# GeekGatheringIot.net
KiCad netlist of a schematic drawn in EAGLE
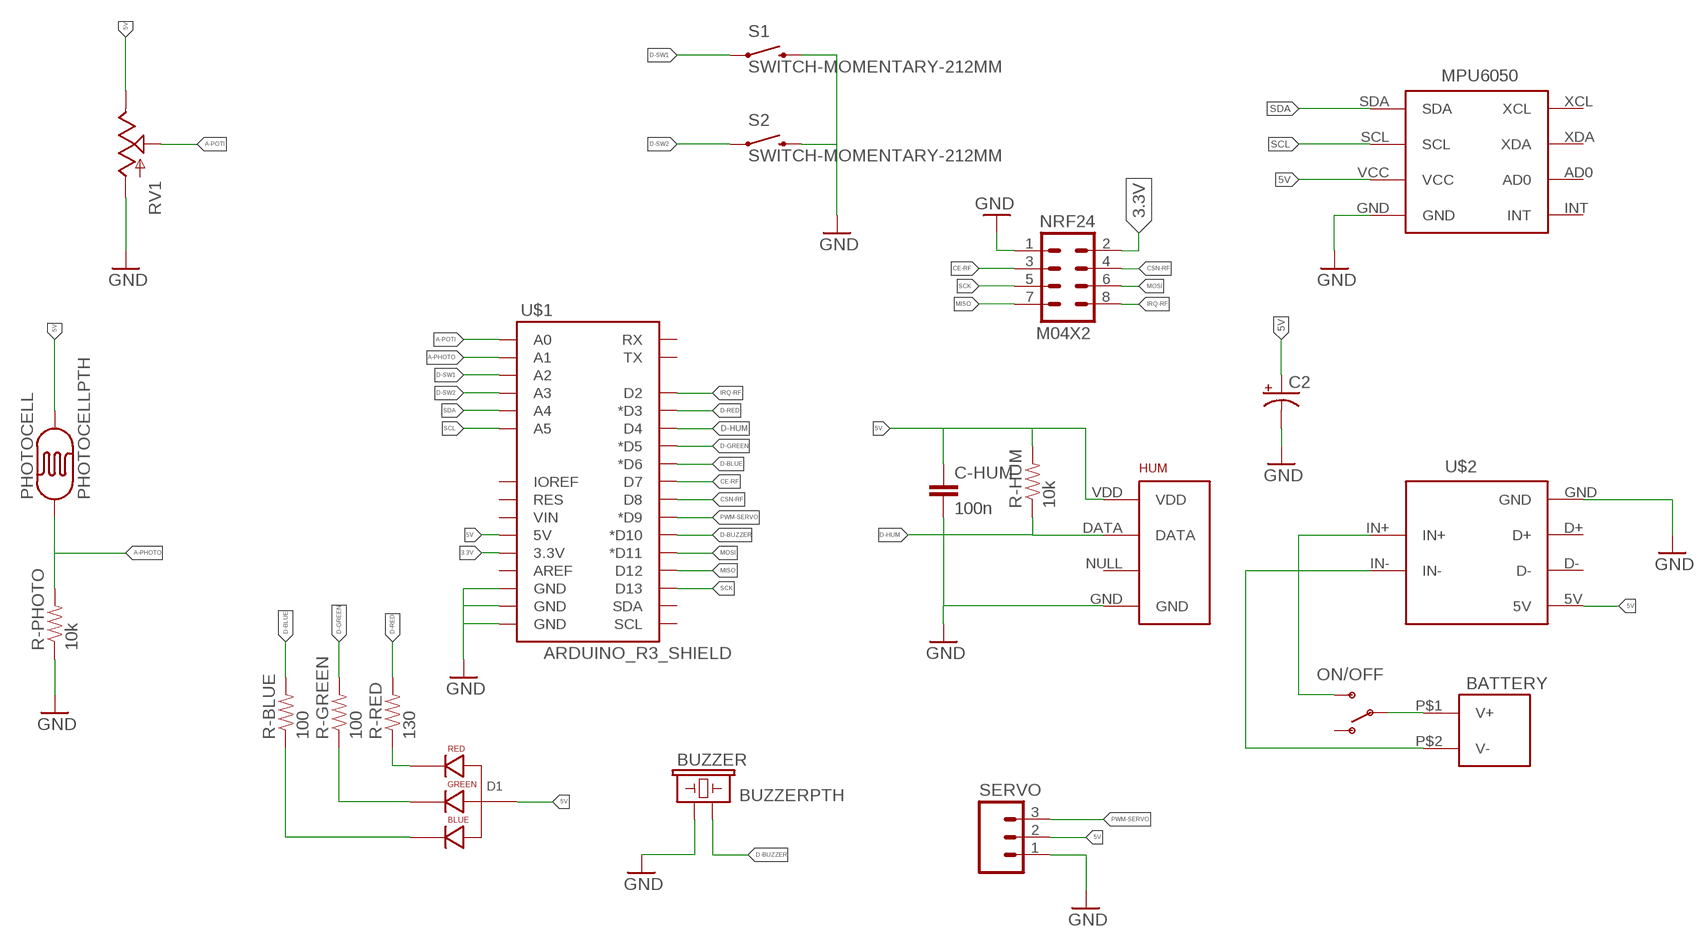
[diagram p0: schematic, sheet 1]

(export (version "E")
  (design (tool "Eeschema 10.0.6"))
  (components
    (comp (ref "BATTERY")
      (value "BATTERY-PACKAAA")
      (footprint "eagle-import:BATTERY-PACK")
      (libsource (lib "eagle-import") (part "BATTERY-PACKAAA"))
    )
    (comp (ref "BUZZER")
      (value "BUZZERPTH")
      (footprint "eagle-import:BUZZER-12MM")
      (libsource (lib "eagle-import") (part "BUZZERPTH"))
    )
    (comp (ref "C-HUM")
      (value "100n")
      (footprint "eagle-import:CAP-PTH-SMALL")
      (libsource (lib "eagle-import") (part "CAPPTH"))
    )
    (comp (ref "C2")
      (value "CAP_POLPTH2")
      (footprint "eagle-import:CPOL-RADIAL-10UF-25V")
      (libsource (lib "eagle-import") (part "CAP_POLPTH2"))
    )
    (comp (ref "D1")
      (value "LED-RGB-CA-THRUCLEAR")
      (footprint "eagle-import:LED-RGB-THRU")
      (libsource (lib "eagle-import") (part "LED-RGB-CA-THRUCLEAR"))
    )
    (comp (ref "HUM")
      (value "RHT03_DHT-22_AM2302")
      (footprint "eagle-import:RHT03_DHT-22")
      (libsource (lib "eagle-import") (part "RHT03_DHT-22_AM2302"))
    )
    (comp (ref "MPU6050")
      (value "MPU6050")
      (footprint "eagle-import:MPU6050")
      (libsource (lib "eagle-import") (part "MPU6050"))
    )
    (comp (ref "NRF24")
      (value "M04X2")
      (footprint "eagle-import:2X4")
      (libsource (lib "eagle-import") (part "M04X2"))
    )
    (comp (ref "ON/OFF")
      (value "SWITCH-SPDTPTH")
      (footprint "eagle-import:SWITCH-SPDT")
      (libsource (lib "eagle-import") (part "SWITCH-SPDTPTH"))
    )
    (comp (ref "PHOTOCELL")
      (value "PHOTOCELLPTH")
      (footprint "eagle-import:PHOTOCELL")
      (libsource (lib "eagle-import") (part "PHOTOCELLPTH"))
    )
    (comp (ref "R-BLUE")
      (value "100")
      (footprint "eagle-import:AXIAL-0.5")
      (libsource (lib "eagle-import") (part "RESISTORPTH-1/2W"))
    )
    (comp (ref "R-GREEN")
      (value "100")
      (footprint "eagle-import:AXIAL-0.5")
      (libsource (lib "eagle-import") (part "RESISTORPTH-1/2W"))
    )
    (comp (ref "R-HUM")
      (value "10k")
      (footprint "eagle-import:AXIAL-0.5")
      (libsource (lib "eagle-import") (part "RESISTORPTH-1/2W"))
    )
    (comp (ref "R-PHOTO")
      (value "10k")
      (footprint "eagle-import:AXIAL-0.5")
      (libsource (lib "eagle-import") (part "RESISTORPTH-1/2W"))
    )
    (comp (ref "R-RED")
      (value "130")
      (footprint "eagle-import:AXIAL-0.5")
      (libsource (lib "eagle-import") (part "RESISTORPTH-1/2W"))
    )
    (comp (ref "RV1")
      (value "POT-RV16AF-20")
      (footprint "eagle-import:POT_ALPHA_RV16AF-20")
      (libsource (lib "eagle-import") (part "POT-RV16AF-20"))
    )
    (comp (ref "S1")
      (value "SWITCH-MOMENTARY-212MM")
      (footprint "eagle-import:TACTILE-PTH-12MM")
      (libsource (lib "eagle-import") (part "SWITCH-MOMENTARY-212MM"))
    )
    (comp (ref "S2")
      (value "SWITCH-MOMENTARY-212MM")
      (footprint "eagle-import:TACTILE-PTH-12MM")
      (libsource (lib "eagle-import") (part "SWITCH-MOMENTARY-212MM"))
    )
    (comp (ref "SERVO")
      (value "M03PTH")
      (footprint "eagle-import:1X03")
      (libsource (lib "eagle-import") (part "M03PTH"))
    )
    (comp (ref "U$1")
      (value "ARDUINO_R3_SHIELD")
      (footprint "eagle-import:UNO_R3_SHIELD")
      (libsource (lib "eagle-import") (part "ARDUINO_R3_SHIELD"))
    )
    (comp (ref "U$2")
      (value "DC-DC-5V")
      (footprint "eagle-import:DC-DC-5V")
      (libsource (lib "eagle-import") (part "DC-DC-5V"))
    )
  )
  (nets
    (net (code "1") (name "3.3V") (class "Default")
      (node (ref "NRF24") (pin "2") (pinfunction "2_2") (pintype "passive"))
      (node (ref "U$1") (pin "3.3V") (pinfunction "3.3V_3.3V") (pintype "bidirectional"))
    )
    (net (code "2") (name "5V") (class "Default")
      (node (ref "C-HUM") (pin "1") (pinfunction "1_1") (pintype "passive"))
      (node (ref "C2") (pin "1") (pinfunction "+_1") (pintype "passive"))
      (node (ref "D1") (pin "2") (pinfunction "ANODE_2") (pintype "bidirectional"))
      (node (ref "HUM") (pin "VDD") (pinfunction "VDD_VDD") (pintype "power_in"))
      (node (ref "MPU6050") (pin "VCC") (pinfunction "VCC_VCC") (pintype "bidirectional"))
      (node (ref "PHOTOCELL") (pin "2") (pinfunction "P$2_2") (pintype "bidirectional"))
      (node (ref "R-HUM") (pin "P$2") (pinfunction "2_P$2") (pintype "passive"))
      (node (ref "RV1") (pin "3") (pinfunction "E_3") (pintype "passive"))
      (node (ref "SERVO") (pin "2") (pinfunction "2_2") (pintype "passive"))
      (node (ref "U$1") (pin "5V") (pinfunction "5V_5V") (pintype "bidirectional"))
      (node (ref "U$2") (pin "5V") (pinfunction "5V_5V") (pintype "bidirectional"))
    )
    (net (code "3") (name "A-PHOTO") (class "Default")
      (node (ref "PHOTOCELL") (pin "1") (pinfunction "P$1_1") (pintype "bidirectional"))
      (node (ref "R-PHOTO") (pin "P$2") (pinfunction "2_P$2") (pintype "passive"))
      (node (ref "U$1") (pin "A1") (pinfunction "A1_A1") (pintype "bidirectional"))
    )
    (net (code "4") (name "A-POTI") (class "Default")
      (node (ref "RV1") (pin "2") (pinfunction "S_2") (pintype "passive"))
      (node (ref "U$1") (pin "A0") (pinfunction "A0_A0") (pintype "bidirectional"))
    )
    (net (code "5") (name "CE-RF") (class "Default")
      (node (ref "NRF24") (pin "3") (pinfunction "3_3") (pintype "passive"))
      (node (ref "U$1") (pin "D7") (pinfunction "D7_D7") (pintype "bidirectional"))
    )
    (net (code "6") (name "CSN-RF") (class "Default")
      (node (ref "NRF24") (pin "4") (pinfunction "4_4") (pintype "passive"))
      (node (ref "U$1") (pin "D8") (pinfunction "D8_D8") (pintype "bidirectional"))
    )
    (net (code "7") (name "D-BLUE") (class "Default")
      (node (ref "R-BLUE") (pin "P$2") (pinfunction "2_P$2") (pintype "passive"))
      (node (ref "U$1") (pin "D6") (pinfunction "*D6_D6") (pintype "bidirectional"))
    )
    (net (code "8") (name "D-BUZZER") (class "Default")
      (node (ref "BUZZER") (pin "-") (pinfunction "2_-") (pintype "passive"))
      (node (ref "U$1") (pin "D10") (pinfunction "*D10_D10") (pintype "bidirectional"))
    )
    (net (code "9") (name "D-GREEN") (class "Default")
      (node (ref "R-GREEN") (pin "P$2") (pinfunction "2_P$2") (pintype "passive"))
      (node (ref "U$1") (pin "D5") (pinfunction "*D5_D5") (pintype "bidirectional"))
    )
    (net (code "10") (name "D-HUM") (class "Default")
      (node (ref "HUM") (pin "DATA") (pinfunction "DATA_DATA") (pintype "bidirectional"))
      (node (ref "R-HUM") (pin "P$1") (pinfunction "1_P$1") (pintype "passive"))
      (node (ref "U$1") (pin "D4") (pinfunction "D4_D4") (pintype "bidirectional"))
    )
    (net (code "11") (name "D-RED") (class "Default")
      (node (ref "R-RED") (pin "P$2") (pinfunction "2_P$2") (pintype "passive"))
      (node (ref "U$1") (pin "D3") (pinfunction "*D3_D3") (pintype "bidirectional"))
    )
    (net (code "12") (name "D-SW1") (class "Default")
      (node (ref "S1") (pin "1") (pinfunction "1_1") (pintype "passive"))
      (node (ref "U$1") (pin "A2") (pinfunction "A2_A2") (pintype "bidirectional"))
    )
    (net (code "13") (name "D-SW2") (class "Default")
      (node (ref "S2") (pin "1") (pinfunction "1_1") (pintype "passive"))
      (node (ref "U$1") (pin "A3") (pinfunction "A3_A3") (pintype "bidirectional"))
    )
    (net (code "14") (name "GND") (class "Default")
      (node (ref "BUZZER") (pin "+") (pinfunction "1_+") (pintype "passive"))
      (node (ref "C-HUM") (pin "2") (pinfunction "2_2") (pintype "passive"))
      (node (ref "C2") (pin "2") (pinfunction "-_2") (pintype "passive"))
      (node (ref "HUM") (pin "GND") (pinfunction "GND_GND") (pintype "power_in"))
      (node (ref "MPU6050") (pin "GND") (pinfunction "GND_GND") (pintype "bidirectional"))
      (node (ref "NRF24") (pin "1") (pinfunction "1_1") (pintype "passive"))
      (node (ref "R-PHOTO") (pin "P$1") (pinfunction "1_P$1") (pintype "passive"))
      (node (ref "RV1") (pin "1") (pinfunction "A_1") (pintype "passive"))
      (node (ref "S1") (pin "3") (pinfunction "2_3") (pintype "passive"))
      (node (ref "S2") (pin "3") (pinfunction "2_3") (pintype "passive"))
      (node (ref "SERVO") (pin "1") (pinfunction "1_1") (pintype "passive"))
      (node (ref "U$1") (pin "GND@0") (pinfunction "GND_GND@0") (pintype "bidirectional"))
      (node (ref "U$1") (pin "GND@1") (pinfunction "GND_GND@1") (pintype "bidirectional"))
      (node (ref "U$1") (pin "GND@2") (pinfunction "GND_GND@2") (pintype "bidirectional"))
      (node (ref "U$2") (pin "GND") (pinfunction "GND_GND") (pintype "bidirectional"))
    )
    (net (code "15") (name "IRQ-RF") (class "Default")
      (node (ref "NRF24") (pin "8") (pinfunction "8_8") (pintype "passive"))
      (node (ref "U$1") (pin "D2") (pinfunction "D2_D2") (pintype "bidirectional"))
    )
    (net (code "16") (name "MISO") (class "Default")
      (node (ref "NRF24") (pin "7") (pinfunction "7_7") (pintype "passive"))
      (node (ref "U$1") (pin "D12") (pinfunction "D12_D12") (pintype "bidirectional"))
    )
    (net (code "17") (name "MOSI") (class "Default")
      (node (ref "NRF24") (pin "6") (pinfunction "6_6") (pintype "passive"))
      (node (ref "U$1") (pin "D11") (pinfunction "*D11_D11") (pintype "bidirectional"))
    )
    (net (code "18") (name "Net-(BATTERY-V+)") (class "Default")
      (node (ref "BATTERY") (pin "P$1") (pinfunction "V+_P$1") (pintype "bidirectional"))
      (node (ref "ON/OFF") (pin "2") (pinfunction "P_2") (pintype "passive"))
    )
    (net (code "19") (name "Net-(BATTERY-V-)") (class "Default")
      (node (ref "BATTERY") (pin "P$2") (pinfunction "V-_P$2") (pintype "bidirectional"))
      (node (ref "U$2") (pin "IN-") (pinfunction "IN-_IN-") (pintype "bidirectional"))
    )
    (net (code "20") (name "Net-(D1-BLUE_CATHODE)") (class "Default")
      (node (ref "D1") (pin "4") (pinfunction "BLUE_CATHODE_4") (pintype "bidirectional"))
      (node (ref "R-BLUE") (pin "P$1") (pinfunction "1_P$1") (pintype "passive"))
    )
    (net (code "21") (name "Net-(D1-GREEN_CATHODE)") (class "Default")
      (node (ref "D1") (pin "3") (pinfunction "GREEN_CATHODE_3") (pintype "bidirectional"))
      (node (ref "R-GREEN") (pin "P$1") (pinfunction "1_P$1") (pintype "passive"))
    )
    (net (code "22") (name "Net-(D1-RED_CATHODE)") (class "Default")
      (node (ref "D1") (pin "1") (pinfunction "RED_CATHODE_1") (pintype "bidirectional"))
      (node (ref "R-RED") (pin "P$1") (pinfunction "1_P$1") (pintype "passive"))
    )
    (net (code "23") (name "Net-(ON/OFF-S)") (class "Default")
      (node (ref "ON/OFF") (pin "3") (pinfunction "S_3") (pintype "passive"))
      (node (ref "U$2") (pin "IN+") (pinfunction "IN+_IN+") (pintype "bidirectional"))
    )
    (net (code "24") (name "PWM-SERVO") (class "Default")
      (node (ref "SERVO") (pin "3") (pinfunction "3_3") (pintype "passive"))
      (node (ref "U$1") (pin "D9") (pinfunction "*D9_D9") (pintype "bidirectional"))
    )
    (net (code "25") (name "SCK") (class "Default")
      (node (ref "NRF24") (pin "5") (pinfunction "5_5") (pintype "passive"))
      (node (ref "U$1") (pin "D13") (pinfunction "D13_D13") (pintype "bidirectional"))
    )
    (net (code "26") (name "SCL") (class "Default")
      (node (ref "MPU6050") (pin "SCL") (pinfunction "SCL_SCL") (pintype "bidirectional"))
      (node (ref "U$1") (pin "A5") (pinfunction "A5_A5") (pintype "bidirectional"))
    )
    (net (code "27") (name "SDA") (class "Default")
      (node (ref "MPU6050") (pin "SDA") (pinfunction "SDA_SDA") (pintype "bidirectional"))
      (node (ref "U$1") (pin "A4") (pinfunction "A4_A4") (pintype "bidirectional"))
    )
    (net (code "28") (name "unconnected-(HUM-PadNULL)") (class "Default")
      (node (ref "HUM") (pin "NULL") (pinfunction "NULL_NULL") (pintype "no_connect"))
    )
    (net (code "29") (name "unconnected-(MPU6050-PadAD0)") (class "Default")
      (node (ref "MPU6050") (pin "AD0") (pinfunction "AD0_AD0") (pintype "bidirectional"))
    )
    (net (code "30") (name "unconnected-(MPU6050-PadINT)") (class "Default")
      (node (ref "MPU6050") (pin "INT") (pinfunction "INT_INT") (pintype "bidirectional"))
    )
    (net (code "31") (name "unconnected-(MPU6050-PadXCL)") (class "Default")
      (node (ref "MPU6050") (pin "XCL") (pinfunction "XCL_XCL") (pintype "bidirectional"))
    )
    (net (code "32") (name "unconnected-(MPU6050-PadXDA)") (class "Default")
      (node (ref "MPU6050") (pin "XDA") (pinfunction "XDA_XDA") (pintype "bidirectional"))
    )
    (net (code "33") (name "unconnected-(ON/OFF-O-Pad1)") (class "Default")
      (node (ref "ON/OFF") (pin "1") (pinfunction "O_1") (pintype "passive"))
    )
    (net (code "34") (name "unconnected-(U$1-PadAREF)") (class "Default")
      (node (ref "U$1") (pin "AREF") (pinfunction "AREF_AREF") (pintype "bidirectional"))
    )
    (net (code "35") (name "unconnected-(U$1-PadIOREF)") (class "Default")
      (node (ref "U$1") (pin "IOREF") (pinfunction "IOREF_IOREF") (pintype "bidirectional"))
    )
    (net (code "36") (name "unconnected-(U$1-PadRES)") (class "Default")
      (node (ref "U$1") (pin "RES") (pinfunction "RES_RES") (pintype "bidirectional"))
    )
    (net (code "37") (name "unconnected-(U$1-PadRX)") (class "Default")
      (node (ref "U$1") (pin "RX") (pinfunction "RX_RX") (pintype "bidirectional"))
    )
    (net (code "38") (name "unconnected-(U$1-PadSCL)") (class "Default")
      (node (ref "U$1") (pin "SCL") (pinfunction "SCL_SCL") (pintype "bidirectional"))
    )
    (net (code "39") (name "unconnected-(U$1-PadSDA)") (class "Default")
      (node (ref "U$1") (pin "SDA") (pinfunction "SDA_SDA") (pintype "bidirectional"))
    )
    (net (code "40") (name "unconnected-(U$1-PadTX)") (class "Default")
      (node (ref "U$1") (pin "TX") (pinfunction "TX_TX") (pintype "bidirectional"))
    )
    (net (code "41") (name "unconnected-(U$1-PadVIN)") (class "Default")
      (node (ref "U$1") (pin "VIN") (pinfunction "VIN_VIN") (pintype "bidirectional"))
    )
    (net (code "42") (name "unconnected-(U$2-PadD+)") (class "Default")
      (node (ref "U$2") (pin "D+") (pinfunction "D+_D+") (pintype "bidirectional"))
    )
    (net (code "43") (name "unconnected-(U$2-PadD-)") (class "Default")
      (node (ref "U$2") (pin "D-") (pinfunction "D-_D-") (pintype "bidirectional"))
    )
  )
)
